# LineCliffSensors.net
KiCad netlist of a schematic drawn in Altium Designer
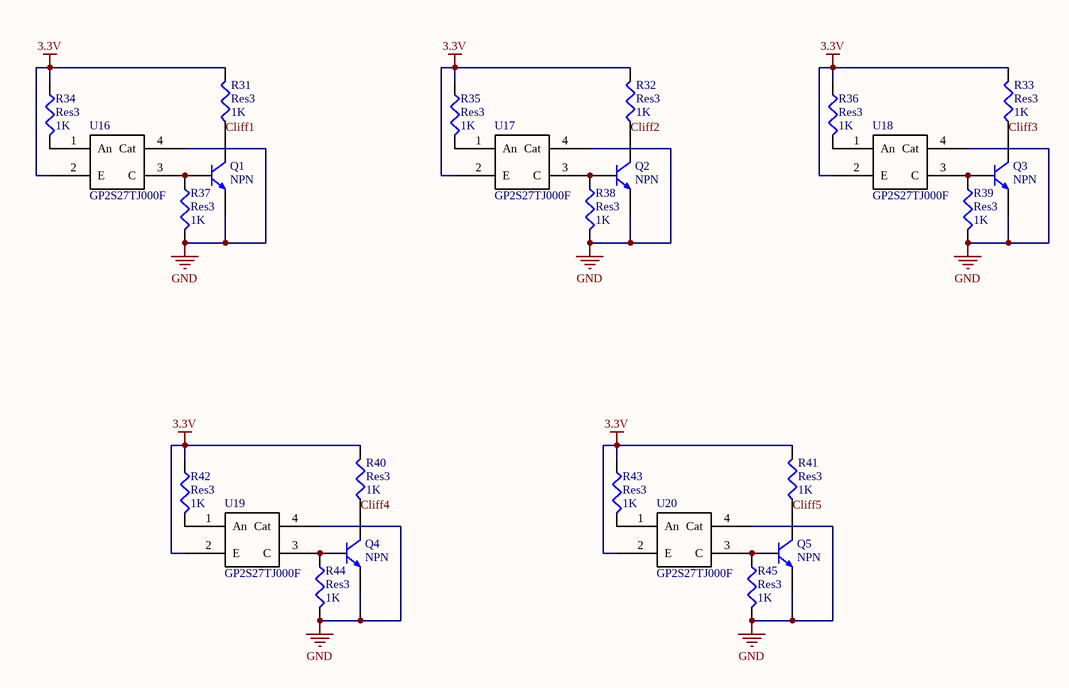
[diagram p0: LineCliffSensors.SchDoc]

(export (version "E")
  (design (tool "Eeschema 10.0.6"))
  (components
    (comp (ref "Q1") (value "NPN") (footprint "SOT-23") (libsource (lib "mrone") (part "NPN")))
    (comp (ref "Q2") (value "NPN") (footprint "SOT-23") (libsource (lib "mrone") (part "NPN")))
    (comp (ref "Q3") (value "NPN") (footprint "SOT-23") (libsource (lib "mrone") (part "NPN")))
    (comp (ref "Q4") (value "NPN") (footprint "SOT-23") (libsource (lib "mrone") (part "NPN")))
    (comp (ref "Q5") (value "NPN") (footprint "SOT-23") (libsource (lib "mrone") (part "NPN")))
    (comp (ref "R31")
      (value "Res3")
      (footprint "RESC1608L")
      (description "Resistor")
      (fields (field (name "ALTIUM_VALUE") "1K") (field (name "PUBLISHER") "Altium Limited"))
      (libsource (lib "Miscellaneous Devices") (part "Res3"))
    )
    (comp (ref "R32")
      (value "Res3")
      (footprint "RESC1608L")
      (description "Resistor")
      (fields (field (name "ALTIUM_VALUE") "1K") (field (name "PUBLISHER") "Altium Limited"))
      (libsource (lib "Miscellaneous Devices") (part "Res3"))
    )
    (comp (ref "R33")
      (value "Res3")
      (footprint "RESC1608L")
      (description "Resistor")
      (fields (field (name "ALTIUM_VALUE") "1K") (field (name "PUBLISHER") "Altium Limited"))
      (libsource (lib "Miscellaneous Devices") (part "Res3"))
    )
    (comp (ref "R34")
      (value "Res3")
      (footprint "RESC1608L")
      (description "Resistor")
      (fields (field (name "ALTIUM_VALUE") "1K") (field (name "PUBLISHER") "Altium Limited"))
      (libsource (lib "Miscellaneous Devices") (part "Res3"))
    )
    (comp (ref "R35")
      (value "Res3")
      (footprint "RESC1608L")
      (description "Resistor")
      (fields (field (name "ALTIUM_VALUE") "1K") (field (name "PUBLISHER") "Altium Limited"))
      (libsource (lib "Miscellaneous Devices") (part "Res3"))
    )
    (comp (ref "R36")
      (value "Res3")
      (footprint "RESC1608L")
      (description "Resistor")
      (fields (field (name "ALTIUM_VALUE") "1K") (field (name "PUBLISHER") "Altium Limited"))
      (libsource (lib "Miscellaneous Devices") (part "Res3"))
    )
    (comp (ref "R37")
      (value "Res3")
      (footprint "RESC1608L")
      (description "Resistor")
      (fields (field (name "ALTIUM_VALUE") "1K") (field (name "PUBLISHER") "Altium Limited"))
      (libsource (lib "Miscellaneous Devices") (part "Res3"))
    )
    (comp (ref "R38")
      (value "Res3")
      (footprint "RESC1608L")
      (description "Resistor")
      (fields (field (name "ALTIUM_VALUE") "1K") (field (name "PUBLISHER") "Altium Limited"))
      (libsource (lib "Miscellaneous Devices") (part "Res3"))
    )
    (comp (ref "R39")
      (value "Res3")
      (footprint "RESC1608L")
      (description "Resistor")
      (fields (field (name "ALTIUM_VALUE") "1K") (field (name "PUBLISHER") "Altium Limited"))
      (libsource (lib "Miscellaneous Devices") (part "Res3"))
    )
    (comp (ref "R40")
      (value "Res3")
      (footprint "RESC1608L")
      (description "Resistor")
      (fields (field (name "ALTIUM_VALUE") "1K") (field (name "PUBLISHER") "Altium Limited"))
      (libsource (lib "Miscellaneous Devices") (part "Res3"))
    )
    (comp (ref "R41")
      (value "Res3")
      (footprint "RESC1608L")
      (description "Resistor")
      (fields (field (name "ALTIUM_VALUE") "1K") (field (name "PUBLISHER") "Altium Limited"))
      (libsource (lib "Miscellaneous Devices") (part "Res3"))
    )
    (comp (ref "R42")
      (value "Res3")
      (footprint "RESC1608L")
      (description "Resistor")
      (fields (field (name "ALTIUM_VALUE") "1K") (field (name "PUBLISHER") "Altium Limited"))
      (libsource (lib "Miscellaneous Devices") (part "Res3"))
    )
    (comp (ref "R43")
      (value "Res3")
      (footprint "RESC1608L")
      (description "Resistor")
      (fields (field (name "ALTIUM_VALUE") "1K") (field (name "PUBLISHER") "Altium Limited"))
      (libsource (lib "Miscellaneous Devices") (part "Res3"))
    )
    (comp (ref "R44")
      (value "Res3")
      (footprint "RESC1608L")
      (description "Resistor")
      (fields (field (name "ALTIUM_VALUE") "1K") (field (name "PUBLISHER") "Altium Limited"))
      (libsource (lib "Miscellaneous Devices") (part "Res3"))
    )
    (comp (ref "R45")
      (value "Res3")
      (footprint "RESC1608L")
      (description "Resistor")
      (fields (field (name "ALTIUM_VALUE") "1K") (field (name "PUBLISHER") "Altium Limited"))
      (libsource (lib "Miscellaneous Devices") (part "Res3"))
    )
    (comp (ref "U16")
      (value "GP2S27TJ000F")
      (footprint "GP2S27J0000F")
      (libsource (lib "mrone") (part "GP2S27TJ000F"))
    )
    (comp (ref "U17")
      (value "GP2S27TJ000F")
      (footprint "GP2S27J0000F")
      (libsource (lib "mrone") (part "GP2S27TJ000F"))
    )
    (comp (ref "U18")
      (value "GP2S27TJ000F")
      (footprint "GP2S27J0000F")
      (libsource (lib "mrone") (part "GP2S27TJ000F"))
    )
    (comp (ref "U19")
      (value "GP2S27TJ000F")
      (footprint "GP2S27J0000F")
      (libsource (lib "mrone") (part "GP2S27TJ000F"))
    )
    (comp (ref "U20")
      (value "GP2S27TJ000F")
      (footprint "GP2S27J0000F")
      (libsource (lib "mrone") (part "GP2S27TJ000F"))
    )
  )
  (nets
    (net (code "1") (name "/Cliff1") (class "Default")
      (node (ref "Q1") (pin "3") (pinfunction "C_3") (pintype "passive"))
      (node (ref "R31") (pin "1") (pinfunction "1_1") (pintype "passive"))
    )
    (net (code "2") (name "/Cliff2") (class "Default")
      (node (ref "Q2") (pin "3") (pinfunction "C_3") (pintype "passive"))
      (node (ref "R32") (pin "1") (pinfunction "1_1") (pintype "passive"))
    )
    (net (code "3") (name "/Cliff3") (class "Default")
      (node (ref "Q3") (pin "3") (pinfunction "C_3") (pintype "passive"))
      (node (ref "R33") (pin "1") (pinfunction "1_1") (pintype "passive"))
    )
    (net (code "4") (name "/Cliff4") (class "Default")
      (node (ref "Q4") (pin "3") (pinfunction "C_3") (pintype "passive"))
      (node (ref "R40") (pin "1") (pinfunction "1_1") (pintype "passive"))
    )
    (net (code "5") (name "/Cliff5") (class "Default")
      (node (ref "Q5") (pin "3") (pinfunction "C_3") (pintype "passive"))
      (node (ref "R41") (pin "1") (pinfunction "1_1") (pintype "passive"))
    )
    (net (code "6") (name "3.3V") (class "Default")
      (node (ref "R31") (pin "2") (pinfunction "2_2") (pintype "passive"))
      (node (ref "R32") (pin "2") (pinfunction "2_2") (pintype "passive"))
      (node (ref "R33") (pin "2") (pinfunction "2_2") (pintype "passive"))
      (node (ref "R34") (pin "1") (pinfunction "1_1") (pintype "passive"))
      (node (ref "R35") (pin "1") (pinfunction "1_1") (pintype "passive"))
      (node (ref "R36") (pin "1") (pinfunction "1_1") (pintype "passive"))
      (node (ref "R40") (pin "2") (pinfunction "2_2") (pintype "passive"))
      (node (ref "R41") (pin "2") (pinfunction "2_2") (pintype "passive"))
      (node (ref "R42") (pin "1") (pinfunction "1_1") (pintype "passive"))
      (node (ref "R43") (pin "1") (pinfunction "1_1") (pintype "passive"))
      (node (ref "U16") (pin "2") (pinfunction "E_2") (pintype "passive"))
      (node (ref "U17") (pin "2") (pinfunction "E_2") (pintype "passive"))
      (node (ref "U18") (pin "2") (pinfunction "E_2") (pintype "passive"))
      (node (ref "U19") (pin "2") (pinfunction "E_2") (pintype "passive"))
      (node (ref "U20") (pin "2") (pinfunction "E_2") (pintype "passive"))
    )
    (net (code "7") (name "GND") (class "Default")
      (node (ref "Q1") (pin "2") (pinfunction "E_2") (pintype "passive"))
      (node (ref "Q2") (pin "2") (pinfunction "E_2") (pintype "passive"))
      (node (ref "Q3") (pin "2") (pinfunction "E_2") (pintype "passive"))
      (node (ref "Q4") (pin "2") (pinfunction "E_2") (pintype "passive"))
      (node (ref "Q5") (pin "2") (pinfunction "E_2") (pintype "passive"))
      (node (ref "R37") (pin "2") (pinfunction "2_2") (pintype "passive"))
      (node (ref "R38") (pin "2") (pinfunction "2_2") (pintype "passive"))
      (node (ref "R39") (pin "2") (pinfunction "2_2") (pintype "passive"))
      (node (ref "R44") (pin "2") (pinfunction "2_2") (pintype "passive"))
      (node (ref "R45") (pin "2") (pinfunction "2_2") (pintype "passive"))
      (node (ref "U16") (pin "4") (pinfunction "Cat_4") (pintype "passive"))
      (node (ref "U17") (pin "4") (pinfunction "Cat_4") (pintype "passive"))
      (node (ref "U18") (pin "4") (pinfunction "Cat_4") (pintype "passive"))
      (node (ref "U19") (pin "4") (pinfunction "Cat_4") (pintype "passive"))
      (node (ref "U20") (pin "4") (pinfunction "Cat_4") (pintype "passive"))
    )
    (net (code "8") (name "Net-(Q1-B)") (class "Default")
      (node (ref "Q1") (pin "1") (pinfunction "B_1") (pintype "passive"))
      (node (ref "R37") (pin "1") (pinfunction "1_1") (pintype "passive"))
      (node (ref "U16") (pin "3") (pinfunction "C_3") (pintype "passive"))
    )
    (net (code "9") (name "Net-(Q2-B)") (class "Default")
      (node (ref "Q2") (pin "1") (pinfunction "B_1") (pintype "passive"))
      (node (ref "R38") (pin "1") (pinfunction "1_1") (pintype "passive"))
      (node (ref "U17") (pin "3") (pinfunction "C_3") (pintype "passive"))
    )
    (net (code "10") (name "Net-(Q3-B)") (class "Default")
      (node (ref "Q3") (pin "1") (pinfunction "B_1") (pintype "passive"))
      (node (ref "R39") (pin "1") (pinfunction "1_1") (pintype "passive"))
      (node (ref "U18") (pin "3") (pinfunction "C_3") (pintype "passive"))
    )
    (net (code "11") (name "Net-(Q4-B)") (class "Default")
      (node (ref "Q4") (pin "1") (pinfunction "B_1") (pintype "passive"))
      (node (ref "R44") (pin "1") (pinfunction "1_1") (pintype "passive"))
      (node (ref "U19") (pin "3") (pinfunction "C_3") (pintype "passive"))
    )
    (net (code "12") (name "Net-(Q5-B)") (class "Default")
      (node (ref "Q5") (pin "1") (pinfunction "B_1") (pintype "passive"))
      (node (ref "R45") (pin "1") (pinfunction "1_1") (pintype "passive"))
      (node (ref "U20") (pin "3") (pinfunction "C_3") (pintype "passive"))
    )
    (net (code "13") (name "Net-(U16-An)") (class "Default")
      (node (ref "R34") (pin "2") (pinfunction "2_2") (pintype "passive"))
      (node (ref "U16") (pin "1") (pinfunction "An_1") (pintype "passive"))
    )
    (net (code "14") (name "Net-(U17-An)") (class "Default")
      (node (ref "R35") (pin "2") (pinfunction "2_2") (pintype "passive"))
      (node (ref "U17") (pin "1") (pinfunction "An_1") (pintype "passive"))
    )
    (net (code "15") (name "Net-(U18-An)") (class "Default")
      (node (ref "R36") (pin "2") (pinfunction "2_2") (pintype "passive"))
      (node (ref "U18") (pin "1") (pinfunction "An_1") (pintype "passive"))
    )
    (net (code "16") (name "Net-(U19-An)") (class "Default")
      (node (ref "R42") (pin "2") (pinfunction "2_2") (pintype "passive"))
      (node (ref "U19") (pin "1") (pinfunction "An_1") (pintype "passive"))
    )
    (net (code "17") (name "Net-(U20-An)") (class "Default")
      (node (ref "R43") (pin "2") (pinfunction "2_2") (pintype "passive"))
      (node (ref "U20") (pin "1") (pinfunction "An_1") (pintype "passive"))
    )
  )
)
